# Connections.net
KiCad netlist of a schematic drawn in Altium Designer
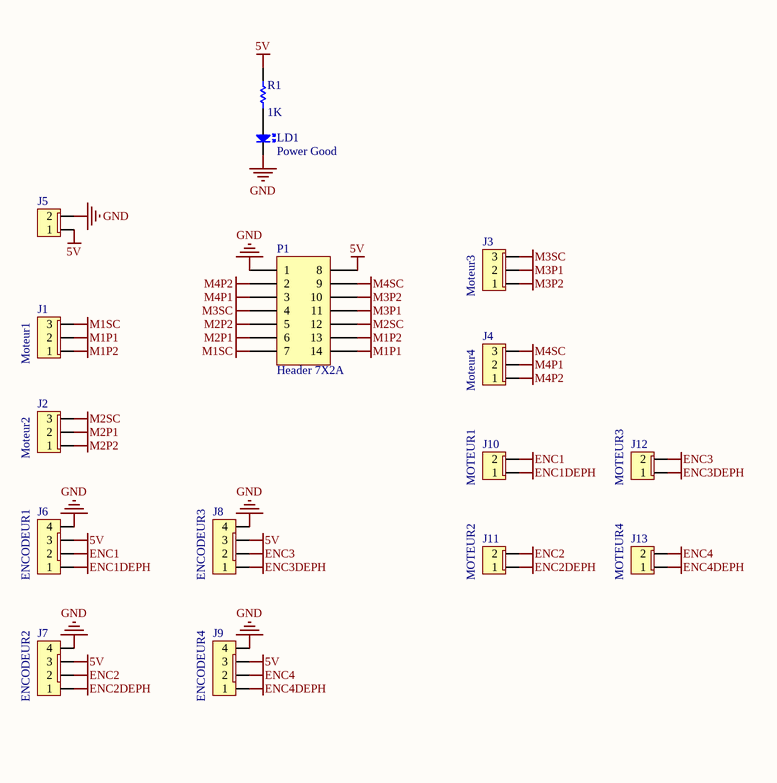
[diagram p0: Connections.SchDoc]

(export (version "E")
  (design (tool "Eeschema 10.0.6"))
  (components
    (comp (ref "J1")
      (value "Moteur1")
      (footprint "MTA100-3 M")
      (description "MTA Male 0 Degres")
      (libsource (lib "Lib Sch") (part "MTA100-3"))
    )
    (comp (ref "J2")
      (value "Moteur2")
      (footprint "MTA100-3 M")
      (description "MTA Male 0 Degres")
      (libsource (lib "Lib Sch") (part "MTA100-3"))
    )
    (comp (ref "J3")
      (value "Moteur3")
      (footprint "MTA100-3 M")
      (description "MTA Male 0 Degres")
      (libsource (lib "Lib Sch") (part "MTA100-3"))
    )
    (comp (ref "J4")
      (value "Moteur4")
      (footprint "MTA100-3 M")
      (description "MTA Male 0 Degres")
      (libsource (lib "Lib Sch") (part "MTA100-3"))
    )
    (comp (ref "J5")
      (value "Input")
      (footprint "MTA100-2")
      (description "MTA Male 0 Degres")
      (libsource (lib "Lib Sch") (part "MTA100-2"))
    )
    (comp (ref "J6")
      (value "ENCODEUR1")
      (footprint "MTA100-4 MF")
      (description "MTA100-4M")
      (libsource (lib "Lib Sch") (part "MTA100-4"))
    )
    (comp (ref "J7")
      (value "ENCODEUR2")
      (footprint "MTA100-4 MF")
      (description "MTA100-4M")
      (libsource (lib "Lib Sch") (part "MTA100-4"))
    )
    (comp (ref "J8")
      (value "ENCODEUR3")
      (footprint "MTA100-4 MF")
      (description "MTA100-4M")
      (libsource (lib "Lib Sch") (part "MTA100-4"))
    )
    (comp (ref "J9")
      (value "ENCODEUR4")
      (footprint "MTA100-4 MF")
      (description "MTA100-4M")
      (libsource (lib "Lib Sch") (part "MTA100-4"))
    )
    (comp (ref "J10")
      (value "MOTEUR1")
      (footprint "MTA100-2")
      (description "MTA Male 0 Degres")
      (libsource (lib "Lib Sch") (part "MTA100-2"))
    )
    (comp (ref "J11")
      (value "MOTEUR2")
      (footprint "MTA100-2")
      (description "MTA Male 0 Degres")
      (libsource (lib "Lib Sch") (part "MTA100-2"))
    )
    (comp (ref "J12")
      (value "MOTEUR3")
      (footprint "MTA100-2")
      (description "MTA Male 0 Degres")
      (libsource (lib "Lib Sch") (part "MTA100-2"))
    )
    (comp (ref "J13")
      (value "MOTEUR4")
      (footprint "MTA100-2")
      (description "MTA Male 0 Degres")
      (libsource (lib "Lib Sch") (part "MTA100-2"))
    )
    (comp (ref "LD1")
      (value "Power Good")
      (footprint "LED 3mm Vertical")
      (description "Through Hole")
      (fields (field (name "PUBLISHER") "Altium Limited"))
      (libsource (lib "Lib Sch") (part "LED 3mm Vertical"))
    )
    (comp (ref "P1")
      (value "Header 7X2A")
      (footprint "HDR2X7_CEN")
      (description "Header, 7-Pin, Dual row")
      (fields (field (name "PUBLISHER") "Altium Limited"))
      (libsource (lib "Miscellaneous Connectors") (part "Header 7X2A"))
    )
    (comp (ref "R1")
      (value "1K")
      (footprint "AXIAL-0.3")
      (description "Resistor")
      (fields (field (name "Comment") "Res1") (field (name "PUBLISHER") "Altium Limited"))
      (libsource (lib "Miscellaneous Devices") (part "Res1"))
    )
  )
  (nets
    (net (code "1") (name "5V") (class "Default")
      (node (ref "J5") (pin "1") (pinfunction "1_1") (pintype "passive"))
      (node (ref "J6") (pin "3") (pinfunction "3_3") (pintype "passive"))
      (node (ref "J7") (pin "3") (pinfunction "3_3") (pintype "passive"))
      (node (ref "J8") (pin "3") (pinfunction "3_3") (pintype "passive"))
      (node (ref "J9") (pin "3") (pinfunction "3_3") (pintype "passive"))
      (node (ref "P1") (pin "8") (pinfunction "8_8") (pintype "passive"))
      (node (ref "R1") (pin "2") (pinfunction "2_2") (pintype "passive"))
    )
    (net (code "2") (name "ENC1") (class "Default")
      (node (ref "J10") (pin "2") (pinfunction "2_2") (pintype "passive"))
      (node (ref "J6") (pin "2") (pinfunction "2_2") (pintype "passive"))
    )
    (net (code "3") (name "ENC1DEPH") (class "Default")
      (node (ref "J10") (pin "1") (pinfunction "1_1") (pintype "passive"))
      (node (ref "J6") (pin "1") (pinfunction "1_1") (pintype "passive"))
    )
    (net (code "4") (name "ENC2") (class "Default")
      (node (ref "J11") (pin "2") (pinfunction "2_2") (pintype "passive"))
      (node (ref "J7") (pin "2") (pinfunction "2_2") (pintype "passive"))
    )
    (net (code "5") (name "ENC2DEPH") (class "Default")
      (node (ref "J11") (pin "1") (pinfunction "1_1") (pintype "passive"))
      (node (ref "J7") (pin "1") (pinfunction "1_1") (pintype "passive"))
    )
    (net (code "6") (name "ENC3") (class "Default")
      (node (ref "J12") (pin "2") (pinfunction "2_2") (pintype "passive"))
      (node (ref "J8") (pin "2") (pinfunction "2_2") (pintype "passive"))
    )
    (net (code "7") (name "ENC3DEPH") (class "Default")
      (node (ref "J12") (pin "1") (pinfunction "1_1") (pintype "passive"))
      (node (ref "J8") (pin "1") (pinfunction "1_1") (pintype "passive"))
    )
    (net (code "8") (name "ENC4") (class "Default")
      (node (ref "J13") (pin "2") (pinfunction "2_2") (pintype "passive"))
      (node (ref "J9") (pin "2") (pinfunction "2_2") (pintype "passive"))
    )
    (net (code "9") (name "ENC4DEPH") (class "Default")
      (node (ref "J13") (pin "1") (pinfunction "1_1") (pintype "passive"))
      (node (ref "J9") (pin "1") (pinfunction "1_1") (pintype "passive"))
    )
    (net (code "10") (name "GND") (class "Default")
      (node (ref "J5") (pin "2") (pinfunction "2_2") (pintype "passive"))
      (node (ref "J6") (pin "4") (pinfunction "4_4") (pintype "passive"))
      (node (ref "J7") (pin "4") (pinfunction "4_4") (pintype "passive"))
      (node (ref "J8") (pin "4") (pinfunction "4_4") (pintype "passive"))
      (node (ref "J9") (pin "4") (pinfunction "4_4") (pintype "passive"))
      (node (ref "LD1") (pin "2") (pinfunction "K_2") (pintype "passive"))
      (node (ref "P1") (pin "1") (pinfunction "1_1") (pintype "passive"))
    )
    (net (code "11") (name "M1P1") (class "Default")
      (node (ref "J1") (pin "2") (pinfunction "2_2") (pintype "passive"))
      (node (ref "P1") (pin "14") (pinfunction "14_14") (pintype "passive"))
    )
    (net (code "12") (name "M1P2") (class "Default")
      (node (ref "J1") (pin "1") (pinfunction "1_1") (pintype "passive"))
      (node (ref "P1") (pin "13") (pinfunction "13_13") (pintype "passive"))
    )
    (net (code "13") (name "M1SC") (class "Default")
      (node (ref "J1") (pin "3") (pinfunction "3_3") (pintype "passive"))
      (node (ref "P1") (pin "7") (pinfunction "7_7") (pintype "passive"))
    )
    (net (code "14") (name "M2P1") (class "Default")
      (node (ref "J2") (pin "2") (pinfunction "2_2") (pintype "passive"))
      (node (ref "P1") (pin "6") (pinfunction "6_6") (pintype "passive"))
    )
    (net (code "15") (name "M2P2") (class "Default")
      (node (ref "J2") (pin "1") (pinfunction "1_1") (pintype "passive"))
      (node (ref "P1") (pin "5") (pinfunction "5_5") (pintype "passive"))
    )
    (net (code "16") (name "M2SC") (class "Default")
      (node (ref "J2") (pin "3") (pinfunction "3_3") (pintype "passive"))
      (node (ref "P1") (pin "12") (pinfunction "12_12") (pintype "passive"))
    )
    (net (code "17") (name "M3P1") (class "Default")
      (node (ref "J3") (pin "2") (pinfunction "2_2") (pintype "passive"))
      (node (ref "P1") (pin "11") (pinfunction "11_11") (pintype "passive"))
    )
    (net (code "18") (name "M3P2") (class "Default")
      (node (ref "J3") (pin "1") (pinfunction "1_1") (pintype "passive"))
      (node (ref "P1") (pin "10") (pinfunction "10_10") (pintype "passive"))
    )
    (net (code "19") (name "M3SC") (class "Default")
      (node (ref "J3") (pin "3") (pinfunction "3_3") (pintype "passive"))
      (node (ref "P1") (pin "4") (pinfunction "4_4") (pintype "passive"))
    )
    (net (code "20") (name "M4P1") (class "Default")
      (node (ref "J4") (pin "2") (pinfunction "2_2") (pintype "passive"))
      (node (ref "P1") (pin "3") (pinfunction "3_3") (pintype "passive"))
    )
    (net (code "21") (name "M4P2") (class "Default")
      (node (ref "J4") (pin "1") (pinfunction "1_1") (pintype "passive"))
      (node (ref "P1") (pin "2") (pinfunction "2_2") (pintype "passive"))
    )
    (net (code "22") (name "M4SC") (class "Default")
      (node (ref "J4") (pin "3") (pinfunction "3_3") (pintype "passive"))
      (node (ref "P1") (pin "9") (pinfunction "9_9") (pintype "passive"))
    )
    (net (code "23") (name "Net-(LD1-A)") (class "Default")
      (node (ref "LD1") (pin "1") (pinfunction "A_1") (pintype "passive"))
      (node (ref "R1") (pin "1") (pinfunction "1_1") (pintype "passive"))
    )
  )
)
